# Bus_Stop_Kiosk_Rev_2.net
KiCad netlist of a schematic drawn in EAGLE
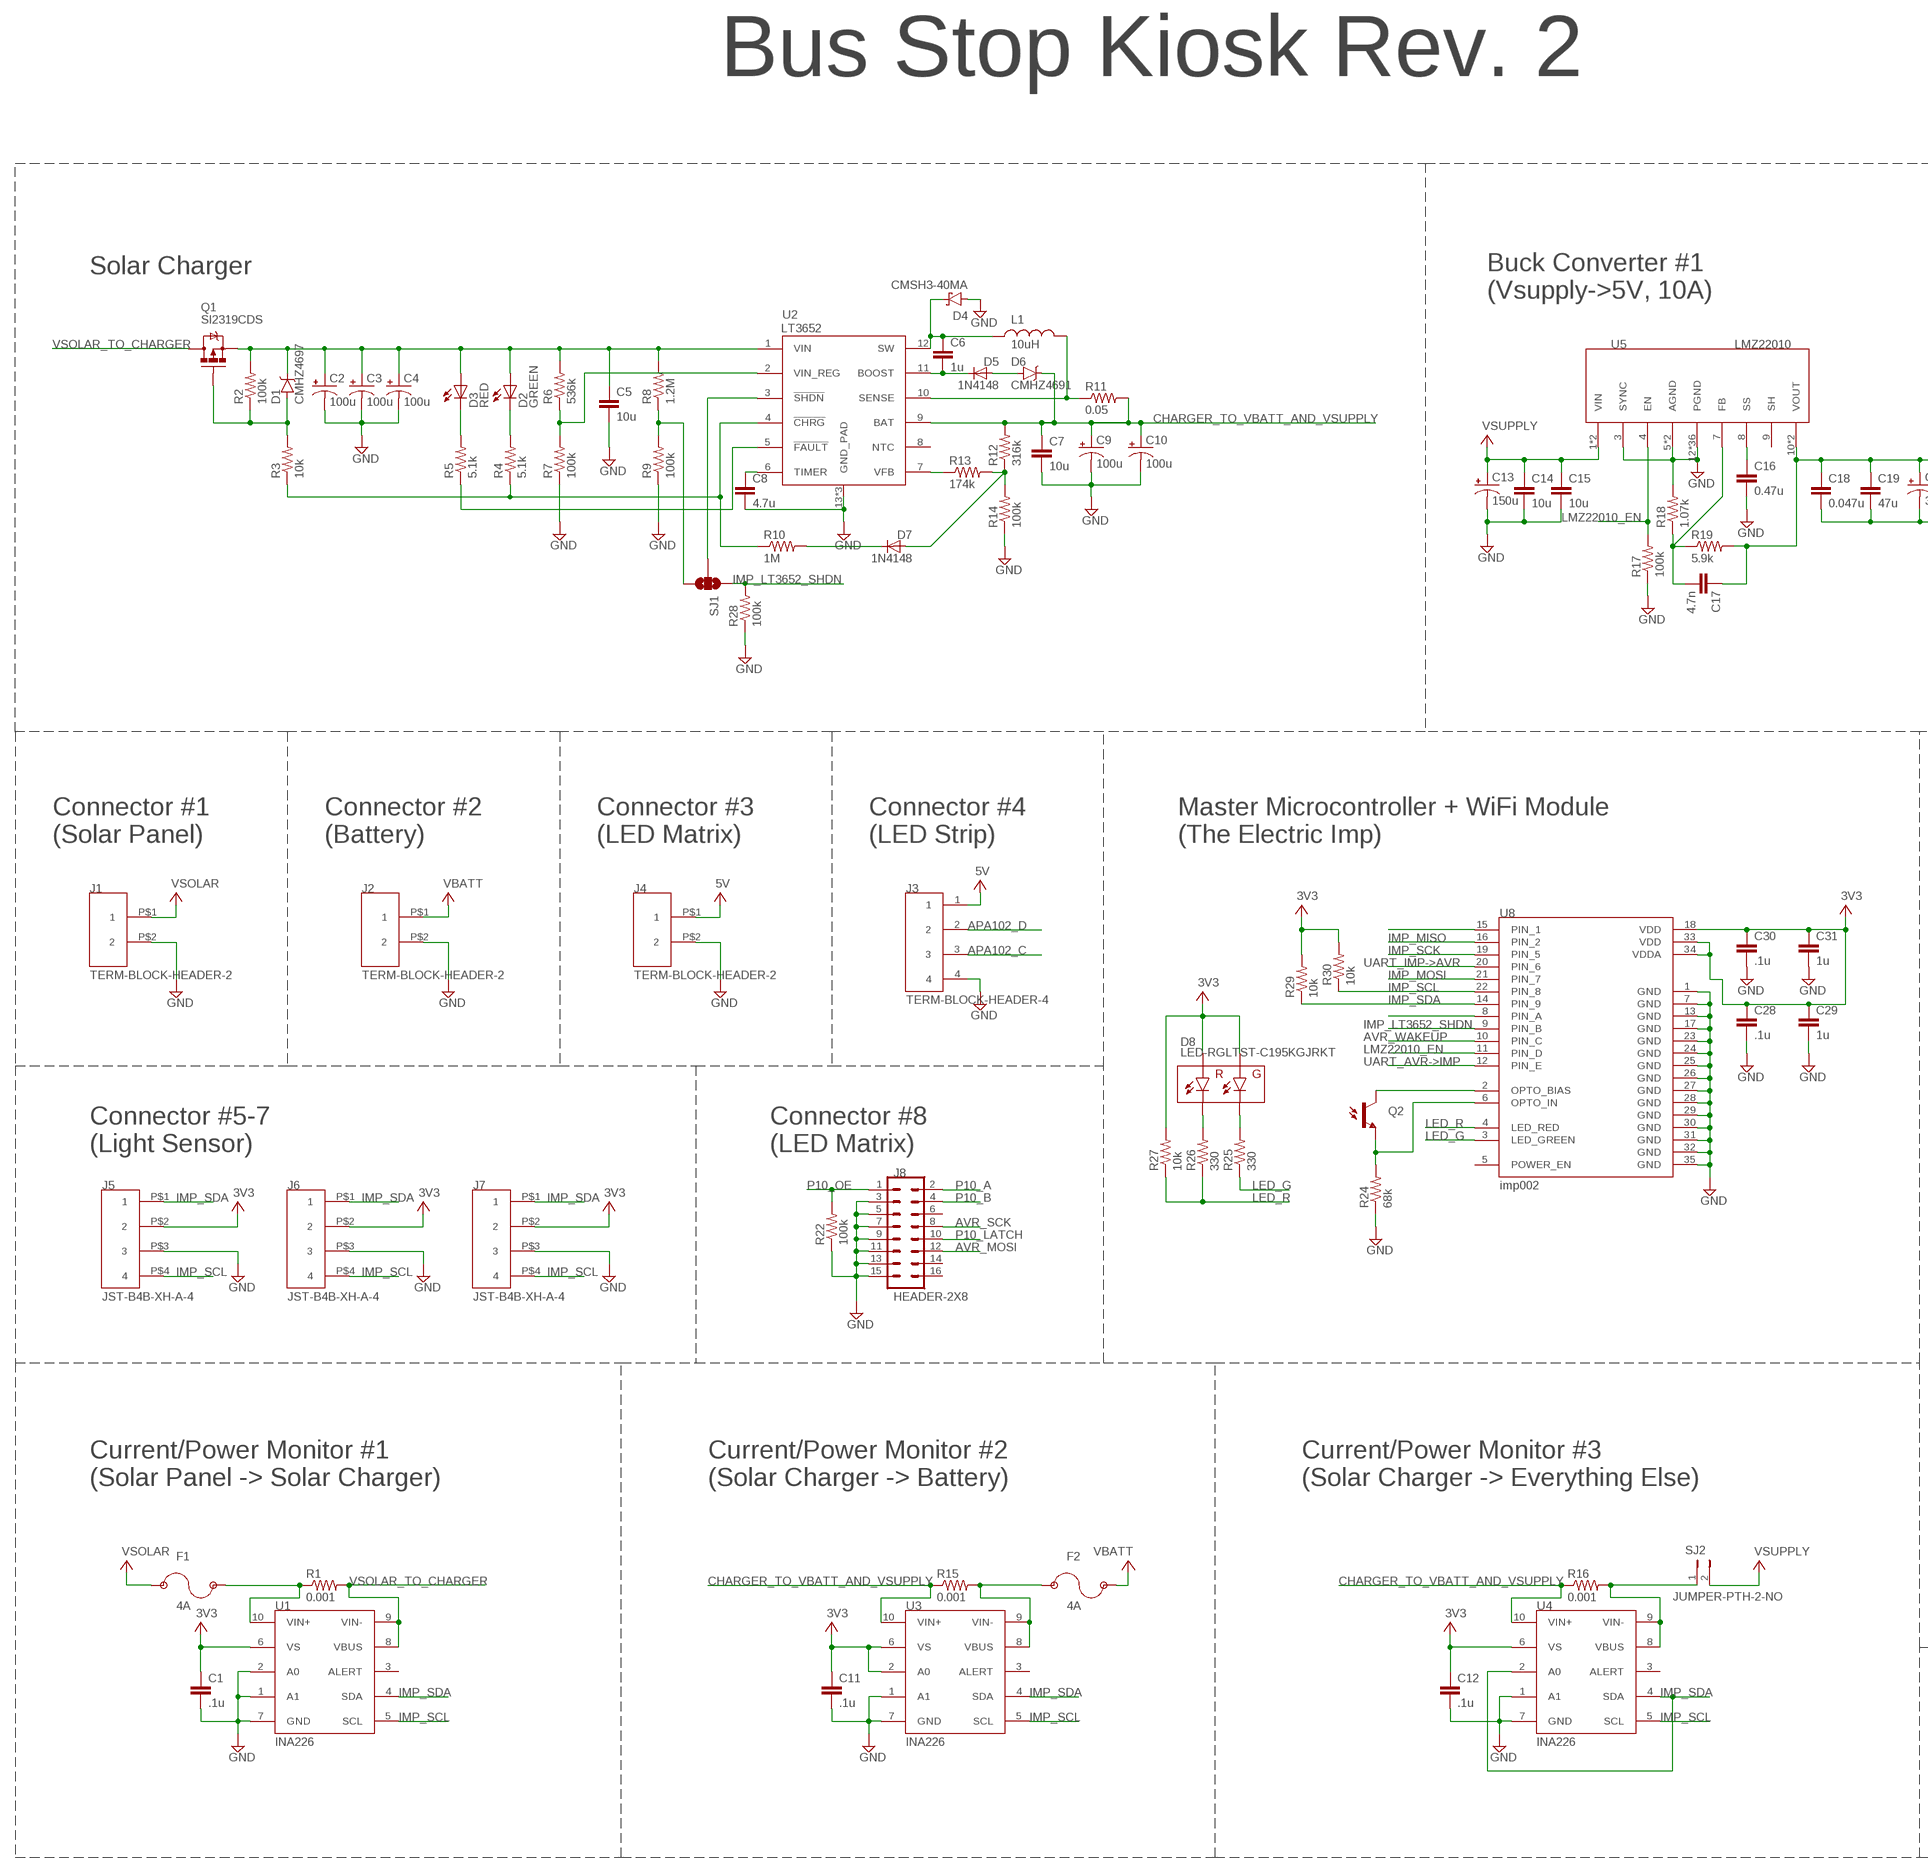
[diagram p0: schematic, sheet 1, part 1 of 2]
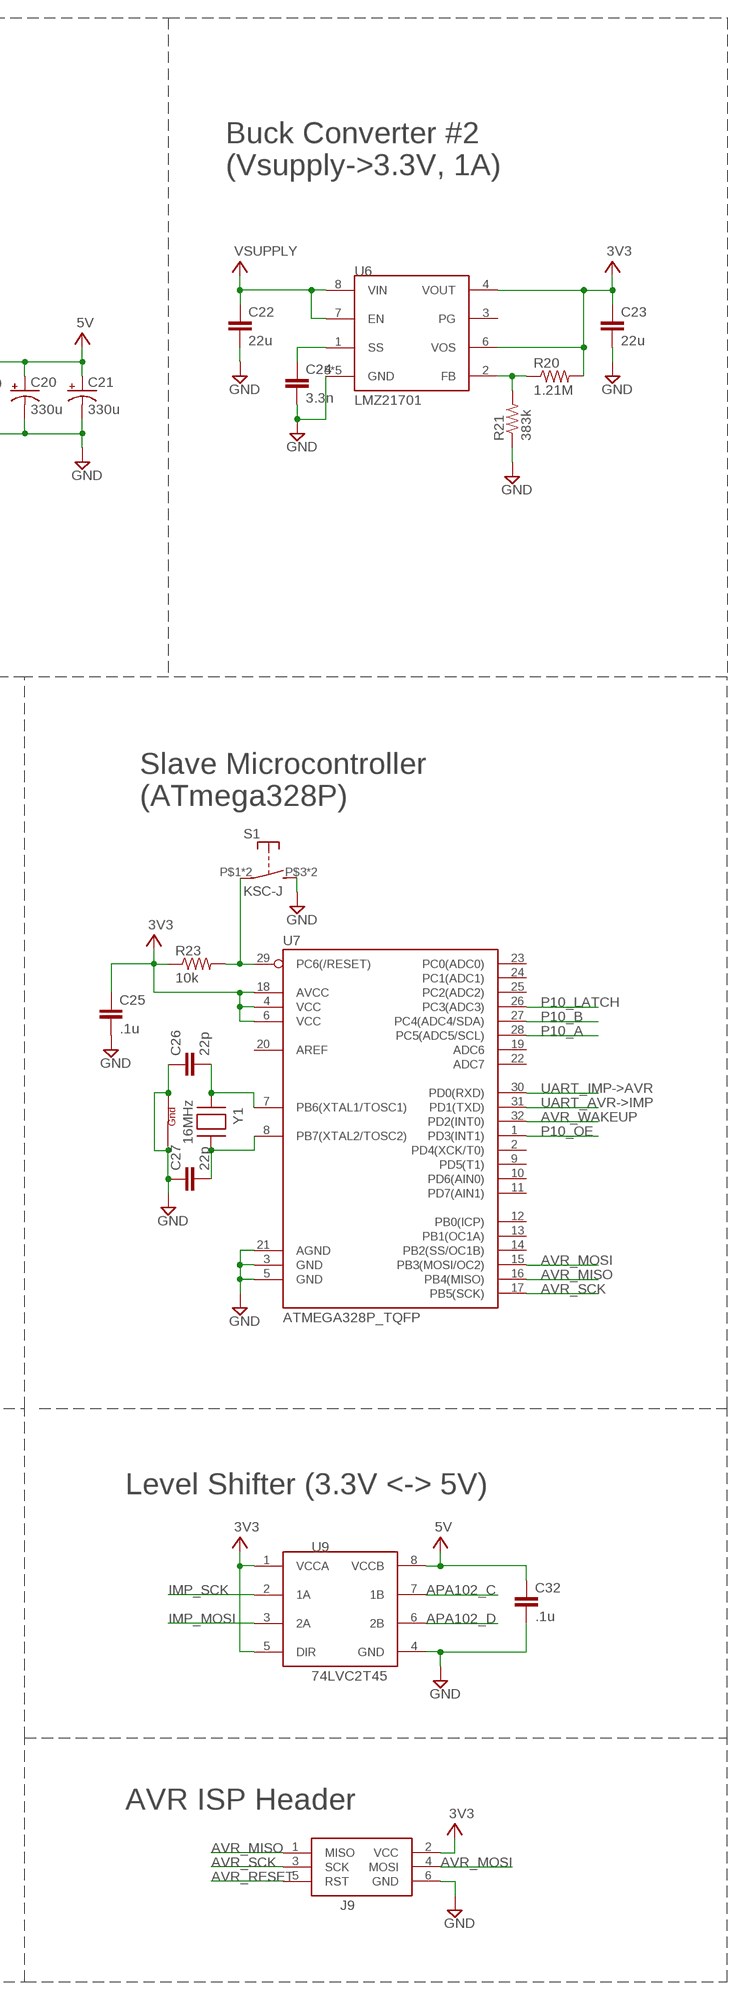
[diagram p1: schematic, sheet 1, part 2 of 2]

(export (version "E")
  (design (tool "Eeschema 10.0.6"))
  (components
    (comp (ref "C1")
      (value ".1u")
      (footprint "eagle-import:C0603K")
      (libsource (lib "eagle-import") (part "C-EUC0603K"))
    )
    (comp (ref "C2")
      (value "100u")
      (footprint "eagle-import:EIA7343")
      (libsource (lib "eagle-import") (part "CAP_POL7343"))
    )
    (comp (ref "C3")
      (value "100u")
      (footprint "eagle-import:EIA7343")
      (libsource (lib "eagle-import") (part "CAP_POL7343"))
    )
    (comp (ref "C4")
      (value "100u")
      (footprint "eagle-import:EIA7343")
      (libsource (lib "eagle-import") (part "CAP_POL7343"))
    )
    (comp (ref "C5")
      (value "10u")
      (footprint "eagle-import:C1210K")
      (libsource (lib "eagle-import") (part "C-EUC1210K"))
    )
    (comp (ref "C6")
      (value "1u")
      (footprint "eagle-import:C0805K")
      (libsource (lib "eagle-import") (part "C-EUC0805K"))
    )
    (comp (ref "C7")
      (value "10u")
      (footprint "eagle-import:C1210K")
      (libsource (lib "eagle-import") (part "C-EUC1210K"))
    )
    (comp (ref "C8")
      (value "4.7u")
      (footprint "eagle-import:C0603K")
      (libsource (lib "eagle-import") (part "C-EUC0603K"))
    )
    (comp (ref "C9")
      (value "100u")
      (footprint "eagle-import:EIA7343")
      (libsource (lib "eagle-import") (part "CAP_POL7343"))
    )
    (comp (ref "C10")
      (value "100u")
      (footprint "eagle-import:EIA7343")
      (libsource (lib "eagle-import") (part "CAP_POL7343"))
    )
    (comp (ref "C11")
      (value ".1u")
      (footprint "eagle-import:C0603K")
      (libsource (lib "eagle-import") (part "C-EUC0603K"))
    )
    (comp (ref "C12")
      (value ".1u")
      (footprint "eagle-import:C0603K")
      (libsource (lib "eagle-import") (part "C-EUC0603K"))
    )
    (comp (ref "C13")
      (value "150u")
      (footprint "eagle-import:PANASONIC_G")
      (libsource (lib "eagle-import") (part "CAP_POLG"))
    )
    (comp (ref "C14")
      (value "10u")
      (footprint "eagle-import:C1210K")
      (libsource (lib "eagle-import") (part "C-EUC1210K"))
    )
    (comp (ref "C15")
      (value "10u")
      (footprint "eagle-import:C1210K")
      (libsource (lib "eagle-import") (part "C-EUC1210K"))
    )
    (comp (ref "C16")
      (value "0.47u")
      (footprint "eagle-import:C0603K")
      (libsource (lib "eagle-import") (part "C-EUC0603K"))
    )
    (comp (ref "C17")
      (value "4.7n")
      (footprint "eagle-import:C0603K")
      (libsource (lib "eagle-import") (part "C-EUC0603K"))
    )
    (comp (ref "C18")
      (value "0.047u")
      (footprint "eagle-import:C1206K")
      (libsource (lib "eagle-import") (part "C-EUC1206K"))
    )
    (comp (ref "C19")
      (value "47u")
      (footprint "eagle-import:C1210K")
      (libsource (lib "eagle-import") (part "C-EUC1210K"))
    )
    (comp (ref "C20")
      (value "330u")
      (footprint "eagle-import:EIA7343")
      (libsource (lib "eagle-import") (part "CAP_POL7343"))
    )
    (comp (ref "C21")
      (value "330u")
      (footprint "eagle-import:EIA7343")
      (libsource (lib "eagle-import") (part "CAP_POL7343"))
    )
    (comp (ref "C22")
      (value "22u")
      (footprint "eagle-import:C1210K")
      (libsource (lib "eagle-import") (part "C-EUC1210K"))
    )
    (comp (ref "C23")
      (value "22u")
      (footprint "eagle-import:C0805K")
      (libsource (lib "eagle-import") (part "C-EUC0805K"))
    )
    (comp (ref "C24")
      (value "3.3n")
      (footprint "eagle-import:C0603K")
      (libsource (lib "eagle-import") (part "C-EUC0603K"))
    )
    (comp (ref "C25")
      (value ".1u")
      (footprint "eagle-import:C0603K")
      (libsource (lib "eagle-import") (part "C-EUC0603K"))
    )
    (comp (ref "C26")
      (value "22p")
      (footprint "eagle-import:C0603K")
      (libsource (lib "eagle-import") (part "C-EUC0603K"))
    )
    (comp (ref "C27")
      (value "22p")
      (footprint "eagle-import:C0603K")
      (libsource (lib "eagle-import") (part "C-EUC0603K"))
    )
    (comp (ref "C28")
      (value ".1u")
      (footprint "eagle-import:C0603K")
      (libsource (lib "eagle-import") (part "C-EUC0603K"))
    )
    (comp (ref "C29")
      (value "1u")
      (footprint "eagle-import:C0603K")
      (libsource (lib "eagle-import") (part "C-EUC0603K"))
    )
    (comp (ref "C30")
      (value ".1u")
      (footprint "eagle-import:C0603K")
      (libsource (lib "eagle-import") (part "C-EUC0603K"))
    )
    (comp (ref "C31")
      (value "1u")
      (footprint "eagle-import:C0603K")
      (libsource (lib "eagle-import") (part "C-EUC0603K"))
    )
    (comp (ref "C32")
      (value ".1u")
      (footprint "eagle-import:C0603K")
      (libsource (lib "eagle-import") (part "C-EUC0603K"))
    )
    (comp (ref "D1")
      (value "CMHZ4697")
      (footprint "eagle-import:SOD-123")
      (libsource (lib "eagle-import") (part "CMHZ4697"))
    )
    (comp (ref "D2")
      (value "GREEN")
      (footprint "eagle-import:CHIP-LED0603")
      (libsource (lib "eagle-import") (part "LEDCHIP-LED0603"))
    )
    (comp (ref "D3")
      (value "RED")
      (footprint "eagle-import:CHIP-LED0603")
      (libsource (lib "eagle-import") (part "LEDCHIP-LED0603"))
    )
    (comp (ref "D4")
      (value "CMSH3-40MA")
      (footprint "eagle-import:SMA-DIODE")
      (libsource (lib "eagle-import") (part "DIODE-SCHOTTKY-B340A"))
    )
    (comp (ref "D5")
      (value "1N4148")
      (footprint "eagle-import:SOD-123")
      (libsource (lib "eagle-import") (part "1N4148"))
    )
    (comp (ref "D6")
      (value "CMHZ4691")
      (footprint "eagle-import:SOD-123")
      (libsource (lib "eagle-import") (part "CMHZ4691"))
    )
    (comp (ref "D7")
      (value "1N4148")
      (footprint "eagle-import:SOD-123")
      (libsource (lib "eagle-import") (part "1N4148"))
    )
    (comp (ref "D8")
      (value "LED-RGLTST-C195KGJRKT")
      (footprint "eagle-import:LTST-C195KGJRKT")
      (libsource (lib "eagle-import") (part "LED-RGLTST-C195KGJRKT"))
    )
    (comp (ref "F1")
      (value "4A")
      (footprint "eagle-import:0603")
      (libsource (lib "eagle-import") (part "FUSE"))
    )
    (comp (ref "F2")
      (value "4A")
      (footprint "eagle-import:0603")
      (libsource (lib "eagle-import") (part "FUSE"))
    )
    (comp (ref "J1")
      (value "TERM-BLOCK-HEADER-2")
      (footprint "eagle-import:TERM-BLOCK-HDR-2")
      (libsource (lib "eagle-import") (part "TERM-BLOCK-HEADER-2"))
    )
    (comp (ref "J2")
      (value "TERM-BLOCK-HEADER-2")
      (footprint "eagle-import:TERM-BLOCK-HDR-2")
      (libsource (lib "eagle-import") (part "TERM-BLOCK-HEADER-2"))
    )
    (comp (ref "J3")
      (value "TERM-BLOCK-HEADER-4")
      (footprint "eagle-import:OSTOQ045451")
      (libsource (lib "eagle-import") (part "TERM-BLOCK-HEADER-4"))
    )
    (comp (ref "J4")
      (value "TERM-BLOCK-HEADER-2")
      (footprint "eagle-import:TERM-BLOCK-HDR-2")
      (libsource (lib "eagle-import") (part "TERM-BLOCK-HEADER-2"))
    )
    (comp (ref "J5")
      (value "JST-B4B-XH-A-4")
      (footprint "eagle-import:JST-B4B-XH-A-4")
      (libsource (lib "eagle-import") (part "JST-B4B-XH-A-4"))
    )
    (comp (ref "J6")
      (value "JST-B4B-XH-A-4")
      (footprint "eagle-import:JST-B4B-XH-A-4")
      (libsource (lib "eagle-import") (part "JST-B4B-XH-A-4"))
    )
    (comp (ref "J7")
      (value "JST-B4B-XH-A-4")
      (footprint "eagle-import:JST-B4B-XH-A-4")
      (libsource (lib "eagle-import") (part "JST-B4B-XH-A-4"))
    )
    (comp (ref "J8")
      (value "HEADER-2X8")
      (footprint "eagle-import:HEADER-2X8-SHROUDED")
      (libsource (lib "eagle-import") (part "HEADER-2X8"))
    )
    (comp (ref "J9")
      (value "AVRISP-6")
      (footprint "eagle-import:AVRISP")
      (libsource (lib "eagle-import") (part "AVRISP-6"))
    )
    (comp (ref "L1")
      (value "10uH")
      (footprint "eagle-import:INDUCTOR-6.86X6.47")
      (libsource (lib "eagle-import") (part "IHLP-2525CZ-01"))
    )
    (comp (ref "Q1")
      (value "SI2319CDS")
      (footprint "eagle-import:SOT-23-3")
      (libsource (lib "eagle-import") (part "SI2319CDS"))
    )
    (comp (ref "Q2")
      (value "PHOTOTRANSISTORPT17-21C-L41-TR8")
      (footprint "eagle-import:PT17-21C-L41-TR8")
      (libsource (lib "eagle-import") (part "PHOTOTRANSISTORPT17-21C-L41-TR8"))
    )
    (comp (ref "R1")
      (value "0.001")
      (footprint "eagle-import:R1206")
      (libsource (lib "eagle-import") (part "R-US_R1206"))
    )
    (comp (ref "R2")
      (value "100k")
      (footprint "eagle-import:R0603")
      (libsource (lib "eagle-import") (part "R-US_R0603"))
    )
    (comp (ref "R3")
      (value "10k")
      (footprint "eagle-import:R0603")
      (libsource (lib "eagle-import") (part "R-US_R0603"))
    )
    (comp (ref "R4")
      (value "5.1k")
      (footprint "eagle-import:R0402")
      (libsource (lib "eagle-import") (part "R-US_R0402"))
    )
    (comp (ref "R5")
      (value "5.1k")
      (footprint "eagle-import:R0402")
      (libsource (lib "eagle-import") (part "R-US_R0402"))
    )
    (comp (ref "R6")
      (value "536k")
      (footprint "eagle-import:R0402")
      (libsource (lib "eagle-import") (part "R-US_R0402"))
    )
    (comp (ref "R7")
      (value "100k")
      (footprint "eagle-import:R0402")
      (libsource (lib "eagle-import") (part "R-US_R0402"))
    )
    (comp (ref "R8")
      (value "1.2M")
      (footprint "eagle-import:R0402")
      (libsource (lib "eagle-import") (part "R-US_R0402"))
    )
    (comp (ref "R9")
      (value "100k")
      (footprint "eagle-import:R0402")
      (libsource (lib "eagle-import") (part "R-US_R0402"))
    )
    (comp (ref "R10")
      (value "1M")
      (footprint "eagle-import:R0402")
      (libsource (lib "eagle-import") (part "R-US_R0402"))
    )
    (comp (ref "R11")
      (value "0.05")
      (footprint "eagle-import:R1206")
      (libsource (lib "eagle-import") (part "R-US_R1206"))
    )
    (comp (ref "R12")
      (value "316k")
      (footprint "eagle-import:R0603")
      (libsource (lib "eagle-import") (part "R-US_R0603"))
    )
    (comp (ref "R13")
      (value "174k")
      (footprint "eagle-import:R0402")
      (libsource (lib "eagle-import") (part "R-US_R0402"))
    )
    (comp (ref "R14")
      (value "100k")
      (footprint "eagle-import:R0603")
      (libsource (lib "eagle-import") (part "R-US_R0603"))
    )
    (comp (ref "R15")
      (value "0.001")
      (footprint "eagle-import:R1206")
      (libsource (lib "eagle-import") (part "R-US_R1206"))
    )
    (comp (ref "R16")
      (value "0.001")
      (footprint "eagle-import:R1206")
      (libsource (lib "eagle-import") (part "R-US_R1206"))
    )
    (comp (ref "R17")
      (value "100k")
      (footprint "eagle-import:R0603")
      (libsource (lib "eagle-import") (part "R-US_R0603"))
    )
    (comp (ref "R18")
      (value "1.07k")
      (footprint "eagle-import:R0603")
      (libsource (lib "eagle-import") (part "R-US_R0603"))
    )
    (comp (ref "R19")
      (value "5.9k")
      (footprint "eagle-import:R0603")
      (libsource (lib "eagle-import") (part "R-US_R0603"))
    )
    (comp (ref "R20")
      (value "1.21M")
      (footprint "eagle-import:R0603")
      (libsource (lib "eagle-import") (part "R-US_R0603"))
    )
    (comp (ref "R21")
      (value "383k")
      (footprint "eagle-import:R0603")
      (libsource (lib "eagle-import") (part "R-US_R0603"))
    )
    (comp (ref "R22")
      (value "100k")
      (footprint "eagle-import:R0603")
      (libsource (lib "eagle-import") (part "R-US_R0603"))
    )
    (comp (ref "R23")
      (value "10k")
      (footprint "eagle-import:R0603")
      (libsource (lib "eagle-import") (part "R-US_R0603"))
    )
    (comp (ref "R24")
      (value "68k")
      (footprint "eagle-import:R0603")
      (libsource (lib "eagle-import") (part "R-US_R0603"))
    )
    (comp (ref "R25")
      (value "330")
      (footprint "eagle-import:R0603")
      (libsource (lib "eagle-import") (part "R-US_R0603"))
    )
    (comp (ref "R26")
      (value "330")
      (footprint "eagle-import:R0603")
      (libsource (lib "eagle-import") (part "R-US_R0603"))
    )
    (comp (ref "R27")
      (value "10k")
      (footprint "eagle-import:R0603")
      (libsource (lib "eagle-import") (part "R-US_R0603"))
    )
    (comp (ref "R28")
      (value "100k")
      (footprint "eagle-import:R0603")
      (libsource (lib "eagle-import") (part "R-US_R0603"))
    )
    (comp (ref "R29")
      (value "10k")
      (footprint "eagle-import:R0603")
      (libsource (lib "eagle-import") (part "R-US_R0603"))
    )
    (comp (ref "R30")
      (value "10k")
      (footprint "eagle-import:R0603")
      (libsource (lib "eagle-import") (part "R-US_R0603"))
    )
    (comp (ref "S1")
      (value "KSC-J")
      (footprint "eagle-import:C&K-KSC")
      (libsource (lib "eagle-import") (part "KSC-J"))
    )
    (comp (ref "SJ1")
      (value "JUMPER-PAD-3-NOYES_SILK")
      (footprint "eagle-import:PAD-JUMPER-3-NO_YES_SILK")
      (libsource (lib "eagle-import") (part "JUMPER-PAD-3-NOYES_SILK"))
    )
    (comp (ref "SJ2")
      (value "JUMPER-PTH-2-NO")
      (footprint "eagle-import:PTH-JUMPER-2-NO_NO_SILK")
      (libsource (lib "eagle-import") (part "JUMPER-PTH-2-NO"))
    )
    (comp (ref "U1")
      (value "INA226")
      (footprint "eagle-import:VSSOP-10")
      (libsource (lib "eagle-import") (part "INA226"))
    )
    (comp (ref "U2")
      (value "LT3652")
      (footprint "eagle-import:MSOP-12_GND")
      (libsource (lib "eagle-import") (part "LT3652"))
    )
    (comp (ref "U3")
      (value "INA226")
      (footprint "eagle-import:VSSOP-10")
      (libsource (lib "eagle-import") (part "INA226"))
    )
    (comp (ref "U4")
      (value "INA226")
      (footprint "eagle-import:VSSOP-10")
      (libsource (lib "eagle-import") (part "INA226"))
    )
    (comp (ref "U5")
      (value "LMZ22010")
      (footprint "eagle-import:TO-PMOD-11")
      (libsource (lib "eagle-import") (part "LMZ22010"))
    )
    (comp (ref "U6")
      (value "LMZ21701")
      (footprint "eagle-import:SIL0008E")
      (libsource (lib "eagle-import") (part "LMZ21701"))
    )
    (comp (ref "U7")
      (value "ATMEGA328P_TQFP")
      (footprint "eagle-import:TQFP32-08")
      (libsource (lib "eagle-import") (part "ATMEGA328P_TQFP"))
    )
    (comp (ref "U8")
      (value "imp002")
      (footprint "eagle-import:ELECTRIC_IMP_IMP002")
      (libsource (lib "eagle-import") (part "ELECTRIC_IMP_IMP002"))
    )
    (comp (ref "U9")
      (value "74LVC2T45")
      (footprint "eagle-import:VSSOP-8")
      (libsource (lib "eagle-import") (part "74LVC2T45"))
    )
    (comp (ref "Y1")
      (value "16MHz")
      (footprint "eagle-import:NX3225")
      (libsource (lib "eagle-import") (part "XTAL-4-3225"))
    )
  )
  (nets
    (net (code "1") (name "/APA102_C") (class "Default")
      (node (ref "J3") (pin "3") (pinfunction "3_3") (pintype "bidirectional"))
      (node (ref "U9") (pin "7") (pinfunction "1B_7") (pintype "bidirectional"))
    )
    (net (code "2") (name "/APA102_D") (class "Default")
      (node (ref "J3") (pin "2") (pinfunction "2_2") (pintype "bidirectional"))
      (node (ref "U9") (pin "6") (pinfunction "2B_6") (pintype "bidirectional"))
    )
    (net (code "3") (name "/AVR_MISO") (class "Default")
      (node (ref "J9") (pin "1") (pinfunction "MISO_1") (pintype "input"))
      (node (ref "U7") (pin "16") (pinfunction "PB4(MISO)_16") (pintype "bidirectional"))
    )
    (net (code "4") (name "/AVR_MOSI") (class "Default")
      (node (ref "J8") (pin "12") (pinfunction "12_12") (pintype "passive"))
      (node (ref "J9") (pin "4") (pinfunction "MOSI_4") (pintype "output"))
      (node (ref "U7") (pin "15") (pinfunction "PB3(MOSI/OC2)_15") (pintype "bidirectional"))
    )
    (net (code "5") (name "/AVR_RESET") (class "Default")
      (node (ref "J9") (pin "5") (pinfunction "RST_5") (pintype "output"))
      (node (ref "R23") (pin "2") (pinfunction "2_2") (pintype "passive"))
      (node (ref "S1") (pin "P$1") (pinfunction "P_P$1") (pintype "passive"))
      (node (ref "S1") (pin "P$2") (pinfunction "P_P$2") (pintype "passive"))
      (node (ref "U7") (pin "29") (pinfunction "PC6(/RESET)_29") (pintype "bidirectional"))
    )
    (net (code "6") (name "/AVR_SCK") (class "Default")
      (node (ref "J8") (pin "8") (pinfunction "8_8") (pintype "passive"))
      (node (ref "J9") (pin "3") (pinfunction "SCK_3") (pintype "output"))
      (node (ref "U7") (pin "17") (pinfunction "PB5(SCK)_17") (pintype "bidirectional"))
    )
    (net (code "7") (name "/AVR_WAKEUP") (class "Default")
      (node (ref "U7") (pin "32") (pinfunction "PD2(INT0)_32") (pintype "bidirectional"))
      (node (ref "U8") (pin "10") (pinfunction "PIN_C_10") (pintype "bidirectional"))
    )
    (net (code "8") (name "/CHARGER_TO_VBATT_AND_VSUPPLY") (class "Default")
      (node (ref "C10") (pin "A") (pinfunction "+_A") (pintype "passive"))
      (node (ref "C7") (pin "1") (pinfunction "1_1") (pintype "passive"))
      (node (ref "C9") (pin "A") (pinfunction "+_A") (pintype "passive"))
      (node (ref "D6") (pin "C") (pinfunction "C_C") (pintype "passive"))
      (node (ref "R11") (pin "2") (pinfunction "2_2") (pintype "passive"))
      (node (ref "R12") (pin "2") (pinfunction "2_2") (pintype "passive"))
      (node (ref "R15") (pin "1") (pinfunction "1_1") (pintype "passive"))
      (node (ref "R16") (pin "1") (pinfunction "1_1") (pintype "passive"))
      (node (ref "U2") (pin "9") (pinfunction "BAT_9") (pintype "bidirectional"))
      (node (ref "U3") (pin "10") (pinfunction "VIN+_10") (pintype "bidirectional"))
      (node (ref "U4") (pin "10") (pinfunction "VIN+_10") (pintype "bidirectional"))
    )
    (net (code "9") (name "/IMP_LT3652_SHDN") (class "Default")
      (node (ref "R28") (pin "2") (pinfunction "2_2") (pintype "passive"))
      (node (ref "SJ1") (pin "1") (pinfunction "1_1") (pintype "passive"))
      (node (ref "U8") (pin "9") (pinfunction "PIN_B_9") (pintype "bidirectional"))
    )
    (net (code "10") (name "/IMP_MISO") (class "Default")
      (node (ref "U8") (pin "16") (pinfunction "PIN_2_16") (pintype "bidirectional"))
    )
    (net (code "11") (name "/IMP_MOSI") (class "Default")
      (node (ref "U8") (pin "21") (pinfunction "PIN_7_21") (pintype "bidirectional"))
      (node (ref "U9") (pin "3") (pinfunction "2A_3") (pintype "bidirectional"))
    )
    (net (code "12") (name "/IMP_SCK") (class "Default")
      (node (ref "U8") (pin "19") (pinfunction "PIN_5_19") (pintype "bidirectional"))
      (node (ref "U9") (pin "2") (pinfunction "1A_2") (pintype "bidirectional"))
    )
    (net (code "13") (name "/IMP_SCL") (class "Default")
      (node (ref "J5") (pin "P$4") (pinfunction "4_P$4") (pintype "bidirectional"))
      (node (ref "J6") (pin "P$4") (pinfunction "4_P$4") (pintype "bidirectional"))
      (node (ref "J7") (pin "P$4") (pinfunction "4_P$4") (pintype "bidirectional"))
      (node (ref "R30") (pin "1") (pinfunction "1_1") (pintype "passive"))
      (node (ref "U1") (pin "5") (pinfunction "SCL_5") (pintype "bidirectional"))
      (node (ref "U3") (pin "5") (pinfunction "SCL_5") (pintype "bidirectional"))
      (node (ref "U4") (pin "5") (pinfunction "SCL_5") (pintype "bidirectional"))
      (node (ref "U8") (pin "22") (pinfunction "PIN_8_22") (pintype "bidirectional"))
    )
    (net (code "14") (name "/IMP_SDA") (class "Default")
      (node (ref "J5") (pin "P$1") (pinfunction "1_P$1") (pintype "bidirectional"))
      (node (ref "J6") (pin "P$1") (pinfunction "1_P$1") (pintype "bidirectional"))
      (node (ref "J7") (pin "P$1") (pinfunction "1_P$1") (pintype "bidirectional"))
      (node (ref "R29") (pin "1") (pinfunction "1_1") (pintype "passive"))
      (node (ref "U1") (pin "4") (pinfunction "SDA_4") (pintype "bidirectional"))
      (node (ref "U3") (pin "4") (pinfunction "SDA_4") (pintype "bidirectional"))
      (node (ref "U4") (pin "2") (pinfunction "A0_2") (pintype "bidirectional"))
      (node (ref "U4") (pin "4") (pinfunction "SDA_4") (pintype "bidirectional"))
      (node (ref "U8") (pin "14") (pinfunction "PIN_9_14") (pintype "bidirectional"))
    )
    (net (code "15") (name "/LED_G") (class "Default")
      (node (ref "R25") (pin "1") (pinfunction "1_1") (pintype "passive"))
      (node (ref "U8") (pin "3") (pinfunction "LED_GREEN_3") (pintype "bidirectional"))
    )
    (net (code "16") (name "/LED_R") (class "Default")
      (node (ref "R26") (pin "1") (pinfunction "1_1") (pintype "passive"))
      (node (ref "R27") (pin "1") (pinfunction "1_1") (pintype "passive"))
      (node (ref "U8") (pin "4") (pinfunction "LED_RED_4") (pintype "bidirectional"))
    )
    (net (code "17") (name "/LMZ22010_EN") (class "Default")
      (node (ref "R17") (pin "2") (pinfunction "2_2") (pintype "passive"))
      (node (ref "U5") (pin "4") (pinfunction "EN_4") (pintype "bidirectional"))
      (node (ref "U8") (pin "11") (pinfunction "PIN_D_11") (pintype "bidirectional"))
    )
    (net (code "18") (name "/P10_A") (class "Default")
      (node (ref "J8") (pin "2") (pinfunction "2_2") (pintype "passive"))
      (node (ref "U7") (pin "28") (pinfunction "PC5(ADC5/SCL)_28") (pintype "bidirectional"))
    )
    (net (code "19") (name "/P10_B") (class "Default")
      (node (ref "J8") (pin "4") (pinfunction "4_4") (pintype "passive"))
      (node (ref "U7") (pin "27") (pinfunction "PC4(ADC4/SDA)_27") (pintype "bidirectional"))
    )
    (net (code "20") (name "/P10_LATCH") (class "Default")
      (node (ref "J8") (pin "10") (pinfunction "10_10") (pintype "passive"))
      (node (ref "U7") (pin "26") (pinfunction "PC3(ADC3)_26") (pintype "bidirectional"))
    )
    (net (code "21") (name "/P10_OE") (class "Default")
      (node (ref "J8") (pin "1") (pinfunction "1_1") (pintype "passive"))
      (node (ref "R22") (pin "2") (pinfunction "2_2") (pintype "passive"))
      (node (ref "U7") (pin "1") (pinfunction "PD3(INT1)_1") (pintype "bidirectional"))
    )
    (net (code "22") (name "/UART_AVR->IMP") (class "Default")
      (node (ref "U7") (pin "31") (pinfunction "PD1(TXD)_31") (pintype "bidirectional"))
      (node (ref "U8") (pin "12") (pinfunction "PIN_E_12") (pintype "bidirectional"))
    )
    (net (code "23") (name "/UART_IMP->AVR") (class "Default")
      (node (ref "U7") (pin "30") (pinfunction "PD0(RXD)_30") (pintype "bidirectional"))
      (node (ref "U8") (pin "20") (pinfunction "PIN_6_20") (pintype "bidirectional"))
    )
    (net (code "24") (name "/VSOLAR_TO_CHARGER") (class "Default")
      (node (ref "Q1") (pin "3") (pinfunction "D_3") (pintype "passive"))
      (node (ref "R1") (pin "2") (pinfunction "2_2") (pintype "passive"))
      (node (ref "U1") (pin "8") (pinfunction "VBUS_8") (pintype "power_in"))
      (node (ref "U1") (pin "9") (pinfunction "VIN-_9") (pintype "bidirectional"))
    )
    (net (code "25") (name "3V3") (class "Default")
      (node (ref "C1") (pin "1") (pinfunction "1_1") (pintype "passive"))
      (node (ref "C11") (pin "1") (pinfunction "1_1") (pintype "passive"))
      (node (ref "C12") (pin "1") (pinfunction "1_1") (pintype "passive"))
      (node (ref "C23") (pin "1") (pinfunction "1_1") (pintype "passive"))
      (node (ref "C25") (pin "1") (pinfunction "1_1") (pintype "passive"))
      (node (ref "C28") (pin "1") (pinfunction "1_1") (pintype "passive"))
      (node (ref "C29") (pin "1") (pinfunction "1_1") (pintype "passive"))
      (node (ref "C30") (pin "1") (pinfunction "1_1") (pintype "passive"))
      (node (ref "C31") (pin "1") (pinfunction "1_1") (pintype "passive"))
      (node (ref "D8") (pin "P$1") (pinfunction "GA_P$1") (pintype "passive"))
      (node (ref "D8") (pin "P$2") (pinfunction "RA_P$2") (pintype "passive"))
      (node (ref "J5") (pin "P$2") (pinfunction "2_P$2") (pintype "bidirectional"))
      (node (ref "J6") (pin "P$2") (pinfunction "2_P$2") (pintype "bidirectional"))
      (node (ref "J7") (pin "P$2") (pinfunction "2_P$2") (pintype "bidirectional"))
      (node (ref "J9") (pin "2") (pinfunction "VCC_2") (pintype "power_in"))
      (node (ref "R20") (pin "2") (pinfunction "2_2") (pintype "passive"))
      (node (ref "R23") (pin "1") (pinfunction "1_1") (pintype "passive"))
      (node (ref "R27") (pin "2") (pinfunction "2_2") (pintype "passive"))
      (node (ref "R29") (pin "2") (pinfunction "2_2") (pintype "passive"))
      (node (ref "R30") (pin "2") (pinfunction "2_2") (pintype "passive"))
      (node (ref "U1") (pin "6") (pinfunction "VS_6") (pintype "power_in"))
      (node (ref "U3") (pin "2") (pinfunction "A0_2") (pintype "bidirectional"))
      (node (ref "U3") (pin "6") (pinfunction "VS_6") (pintype "power_in"))
      (node (ref "U4") (pin "6") (pinfunction "VS_6") (pintype "power_in"))
      (node (ref "U6") (pin "4") (pinfunction "VOUT_4") (pintype "bidirectional"))
      (node (ref "U6") (pin "6") (pinfunction "VOS_6") (pintype "bidirectional"))
      (node (ref "U7") (pin "18") (pinfunction "AVCC_18") (pintype "bidirectional"))
      (node (ref "U7") (pin "4") (pinfunction "VCC_4") (pintype "bidirectional"))
      (node (ref "U7") (pin "6") (pinfunction "VCC_6") (pintype "bidirectional"))
      (node (ref "U8") (pin "18") (pinfunction "VDD_18") (pintype "bidirectional"))
      (node (ref "U8") (pin "33") (pinfunction "VDD_33") (pintype "bidirectional"))
      (node (ref "U8") (pin "34") (pinfunction "VDDA_34") (pintype "bidirectional"))
      (node (ref "U9") (pin "1") (pinfunction "VCCA_1") (pintype "bidirectional"))
      (node (ref "U9") (pin "5") (pinfunction "DIR_5") (pintype "bidirectional"))
    )
    (net (code "26") (name "5V") (class "Default")
      (node (ref "C17") (pin "1") (pinfunction "1_1") (pintype "passive"))
      (node (ref "C18") (pin "1") (pinfunction "1_1") (pintype "passive"))
      (node (ref "C19") (pin "1") (pinfunction "1_1") (pintype "passive"))
      (node (ref "C20") (pin "A") (pinfunction "+_A") (pintype "passive"))
      (node (ref "C21") (pin "A") (pinfunction "+_A") (pintype "passive"))
      (node (ref "C32") (pin "1") (pinfunction "1_1") (pintype "passive"))
      (node (ref "J3") (pin "1") (pinfunction "1_1") (pintype "bidirectional"))
      (node (ref "J4") (pin "P$1") (pinfunction "1_P$1") (pintype "bidirectional"))
      (node (ref "R19") (pin "2") (pinfunction "2_2") (pintype "passive"))
      (node (ref "U5") (pin "10") (pinfunction "VOUT_10") (pintype "bidirectional"))
      (node (ref "U5") (pin "11") (pinfunction "VOUT_11") (pintype "bidirectional"))
      (node (ref "U9") (pin "8") (pinfunction "VCCB_8") (pintype "bidirectional"))
    )
    (net (code "27") (name "GND") (class "Default")
      (node (ref "C1") (pin "2") (pinfunction "2_2") (pintype "passive"))
      (node (ref "C10") (pin "C") (pinfunction "-_C") (pintype "passive"))
      (node (ref "C11") (pin "2") (pinfunction "2_2") (pintype "passive"))
      (node (ref "C12") (pin "2") (pinfunction "2_2") (pintype "passive"))
      (node (ref "C13") (pin "-") (pinfunction "-_-") (pintype "passive"))
      (node (ref "C14") (pin "2") (pinfunction "2_2") (pintype "passive"))
      (node (ref "C15") (pin "2") (pinfunction "2_2") (pintype "passive"))
      (node (ref "C16") (pin "2") (pinfunction "2_2") (pintype "passive"))
      (node (ref "C18") (pin "2") (pinfunction "2_2") (pintype "passive"))
      (node (ref "C19") (pin "2") (pinfunction "2_2") (pintype "passive"))
      (node (ref "C2") (pin "C") (pinfunction "-_C") (pintype "passive"))
      (node (ref "C20") (pin "C") (pinfunction "-_C") (pintype "passive"))
      (node (ref "C21") (pin "C") (pinfunction "-_C") (pintype "passive"))
      (node (ref "C22") (pin "2") (pinfunction "2_2") (pintype "passive"))
      (node (ref "C23") (pin "2") (pinfunction "2_2") (pintype "passive"))
      (node (ref "C24") (pin "2") (pinfunction "2_2") (pintype "passive"))
      (node (ref "C25") (pin "2") (pinfunction "2_2") (pintype "passive"))
      (node (ref "C26") (pin "1") (pinfunction "1_1") (pintype "passive"))
      (node (ref "C27") (pin "1") (pinfunction "1_1") (pintype "passive"))
      (node (ref "C28") (pin "2") (pinfunction "2_2") (pintype "passive"))
      (node (ref "C29") (pin "2") (pinfunction "2_2") (pintype "passive"))
      (node (ref "C3") (pin "C") (pinfunction "-_C") (pintype "passive"))
      (node (ref "C30") (pin "2") (pinfunction "2_2") (pintype "passive"))
      (node (ref "C31") (pin "2") (pinfunction "2_2") (pintype "passive"))
      (node (ref "C32") (pin "2") (pinfunction "2_2") (pintype "passive"))
      (node (ref "C4") (pin "C") (pinfunction "-_C") (pintype "passive"))
      (node (ref "C5") (pin "2") (pinfunction "2_2") (pintype "passive"))
      (node (ref "C7") (pin "2") (pinfunction "2_2") (pintype "passive"))
      (node (ref "C8") (pin "2") (pinfunction "2_2") (pintype "passive"))
      (node (ref "C9") (pin "C") (pinfunction "-_C") (pintype "passive"))
      (node (ref "D4") (pin "A") (pinfunction "A_A") (pintype "passive"))
      (node (ref "J1") (pin "P$2") (pinfunction "2_P$2") (pintype "bidirectional"))
      (node (ref "J2") (pin "P$2") (pinfunction "2_P$2") (pintype "bidirectional"))
      (node (ref "J3") (pin "4") (pinfunction "4_4") (pintype "bidirectional"))
      (node (ref "J4") (pin "P$2") (pinfunction "2_P$2") (pintype "bidirectional"))
      (node (ref "J5") (pin "P$3") (pinfunction "3_P$3") (pintype "bidirectional"))
      (node (ref "J6") (pin "P$3") (pinfunction "3_P$3") (pintype "bidirectional"))
      (node (ref "J7") (pin "P$3") (pinfunction "3_P$3") (pintype "bidirectional"))
      (node (ref "J8") (pin "11") (pinfunction "11_11") (pintype "passive"))
      (node (ref "J8") (pin "13") (pinfunction "13_13") (pintype "passive"))
      (node (ref "J8") (pin "15") (pinfunction "15_15") (pintype "passive"))
      (node (ref "J8") (pin "3") (pinfunction "3_3") (pintype "passive"))
      (node (ref "J8") (pin "5") (pinfunction "5_5") (pintype "passive"))
      (node (ref "J8") (pin "7") (pinfunction "7_7") (pintype "passive"))
      (node (ref "J8") (pin "9") (pinfunction "9_9") (pintype "passive"))
      (node (ref "J9") (pin "6") (pinfunction "GND_6") (pintype "power_in"))
      (node (ref "R14") (pin "1") (pinfunction "1_1") (pintype "passive"))
      (node (ref "R17") (pin "1") (pinfunction "1_1") (pintype "passive"))
      (node (ref "R18") (pin "2") (pinfunction "2_2") (pintype "passive"))
      (node (ref "R21") (pin "1") (pinfunction "1_1") (pintype "passive"))
      (node (ref "R22") (pin "1") (pinfunction "1_1") (pintype "passive"))
      (node (ref "R24") (pin "1") (pinfunction "1_1") (pintype "passive"))
      (node (ref "R28") (pin "1") (pinfunction "1_1") (pintype "passive"))
      (node (ref "R7") (pin "1") (pinfunction "1_1") (pintype "passive"))
      (node (ref "R9") (pin "1") (pinfunction "1_1") (pintype "passive"))
      (node (ref "S1") (pin "P$3") (pinfunction "S_P$3") (pintype "passive"))
      (node (ref "S1") (pin "P$4") (pinfunction "S_P$4") (pintype "passive"))
      (node (ref "U1") (pin "1") (pinfunction "A1_1") (pintype "bidirectional"))
      (node (ref "U1") (pin "2") (pinfunction "A0_2") (pintype "bidirectional"))
      (node (ref "U1") (pin "7") (pinfunction "GND_7") (pintype "power_in"))
      (node (ref "U2") (pin "13") (pinfunction "GND_PAD_13") (pintype "bidirectional"))
      (node (ref "U2") (pin "P$1") (pinfunction "GND_PAD_P$1") (pintype "bidirectional"))
      (node (ref "U2") (pin "P$2") (pinfunction "GND_PAD_P$2") (pintype "bidirectional"))
      (node (ref "U3") (pin "1") (pinfunction "A1_1") (pintype "bidirectional"))
      (node (ref "U3") (pin "7") (pinfunction "GND_7") (pintype "power_in"))
      (node (ref "U4") (pin "1") (pinfunction "A1_1") (pintype "bidirectional"))
      (node (ref "U4") (pin "7") (pinfunction "GND_7") (pintype "power_in"))
      (node (ref "U5") (pin "12") (pinfunction "PGND_12") (pintype "bidirectional"))
      (node (ref "U5") (pin "3") (pinfunction "SYNC_3") (pintype "bidirectional"))
      (node (ref "U5") (pin "5") (pinfunction "AGND_5") (pintype "bidirectional"))
      (node (ref "U5") (pin "6") (pinfunction "AGND_6") (pintype "bidirectional"))
      (node (ref "U5") (pin "P$1") (pinfunction "PGND_P$1") (pintype "bidirectional"))
      (node (ref "U5") (pin "P$10") (pinfunction "PGND_P$10") (pintype "bidirectional"))
      (node (ref "U5") (pin "P$11") (pinfunction "PGND_P$11") (pintype "bidirectional"))
      (node (ref "U5") (pin "P$12") (pinfunction "PGND_P$12") (pintype "bidirectional"))
      (node (ref "U5") (pin "P$13") (pinfunction "PGND_P$13") (pintype "bidirectional"))
      (node (ref "U5") (pin "P$14") (pinfunction "PGND_P$14") (pintype "bidirectional"))
      (node (ref "U5") (pin "P$15") (pinfunction "PGND_P$15") (pintype "bidirectional"))
      (node (ref "U5") (pin "P$16") (pinfunction "PGND_P$16") (pintype "bidirectional"))
      (node (ref "U5") (pin "P$17") (pinfunction "PGND_P$17") (pintype "bidirectional"))
      (node (ref "U5") (pin "P$18") (pinfunction "PGND_P$18") (pintype "bidirectional"))
      (node (ref "U5") (pin "P$19") (pinfunction "PGND_P$19") (pintype "bidirectional"))
      (node (ref "U5") (pin "P$2") (pinfunction "PGND_P$2") (pintype "bidirectional"))
      (node (ref "U5") (pin "P$20") (pinfunction "PGND_P$20") (pintype "bidirectional"))
      (node (ref "U5") (pin "P$21") (pinfunction "PGND_P$21") (pintype "bidirectional"))
      (node (ref "U5") (pin "P$22") (pinfunction "PGND_P$22") (pintype "bidirectional"))
      (node (ref "U5") (pin "P$23") (pinfunction "PGND_P$23") (pintype "bidirectional"))
      (node (ref "U5") (pin "P$24") (pinfunction "PGND_P$24") (pintype "bidirectional"))
      (node (ref "U5") (pin "P$25") (pinfunction "PGND_P$25") (pintype "bidirectional"))
      (node (ref "U5") (pin "P$26") (pinfunction "PGND_P$26") (pintype "bidirectional"))
      (node (ref "U5") (pin "P$27") (pinfunction "PGND_P$27") (pintype "bidirectional"))
      (node (ref "U5") (pin "P$28") (pinfunction "PGND_P$28") (pintype "bidirectional"))
      (node (ref "U5") (pin "P$29") (pinfunction "PGND_P$29") (pintype "bidirectional"))
      (node (ref "U5") (pin "P$3") (pinfunction "PGND_P$3") (pintype "bidirectional"))
      (node (ref "U5") (pin "P$30") (pinfunction "PGND_P$30") (pintype "bidirectional"))
      (node (ref "U5") (pin "P$31") (pinfunction "PGND_P$31") (pintype "bidirectional"))
      (node (ref "U5") (pin "P$32") (pinfunction "PGND_P$32") (pintype "bidirectional"))
      (node (ref "U5") (pin "P$33") (pinfunction "PGND_P$33") (pintype "bidirectional"))
      (node (ref "U5") (pin "P$34") (pinfunction "PGND_P$34") (pintype "bidirectional"))
      (node (ref "U5") (pin "P$35") (pinfunction "PGND_P$35") (pintype "bidirectional"))
      (node (ref "U5") (pin "P$4") (pinfunction "PGND_P$4") (pintype "bidirectional"))
      (node (ref "U5") (pin "P$5") (pinfunction "PGND_P$5") (pintype "bidirectional"))
      (node (ref "U5") (pin "P$6") (pinfunction "PGND_P$6") (pintype "bidirectional"))
      (node (ref "U5") (pin "P$7") (pinfunction "PGND_P$7") (pintype "bidirectional"))
      (node (ref "U5") (pin "P$8") (pinfunction "PGND_P$8") (pintype "bidirectional"))
      (node (ref "U5") (pin "P$9") (pinfunction "PGND_P$9") (pintype "bidirectional"))
      (node (ref "U6") (pin "10") (pinfunction "GND_10") (pintype "bidirectional"))
      (node (ref "U6") (pin "11") (pinfunction "GND_11") (pintype "bidirectional"))
      (node (ref "U6") (pin "12") (pinfunction "GND_12") (pintype "bidirectional"))
      (node (ref "U6") (pin "5") (pinfunction "GND_5") (pintype "bidirectional"))
      (node (ref "U6") (pin "9") (pinfunction "GND_9") (pintype "bidirectional"))
      (node (ref "U7") (pin "21") (pinfunction "AGND_21") (pintype "bidirectional"))
      (node (ref "U7") (pin "3") (pinfunction "GND_3") (pintype "bidirectional"))
      (node (ref "U7") (pin "5") (pinfunction "GND_5") (pintype "bidirectional"))
      (node (ref "U8") (pin "1") (pinfunction "GND_1") (pintype "bidirectional"))
      (node (ref "U8") (pin "13") (pinfunction "GND_13") (pintype "bidirectional"))
      (node (ref "U8") (pin "17") (pinfunction "GND_17") (pintype "bidirectional"))
      (node (ref "U8") (pin "23") (pinfunction "GND_23") (pintype "bidirectional"))
      (node (ref "U8") (pin "24") (pinfunction "GND_24") (pintype "bidirectional"))
      (node (ref "U8") (pin "25") (pinfunction "GND_25") (pintype "bidirectional"))
      (node (ref "U8") (pin "26") (pinfunction "GND_26") (pintype "bidirectional"))
      (node (ref "U8") (pin "27") (pinfunction "GND_27") (pintype "bidirectional"))
      (node (ref "U8") (pin "28") (pinfunction "GND_28") (pintype "bidirectional"))
      (node (ref "U8") (pin "29") (pinfunction "GND_29") (pintype "bidirectional"))
      (node (ref "U8") (pin "30") (pinfunction "GND_30") (pintype "bidirectional"))
      (node (ref "U8") (pin "31") (pinfunction "GND_31") (pintype "bidirectional"))
      (node (ref "U8") (pin "32") (pinfunction "GND_32") (pintype "bidirectional"))
      (node (ref "U8") (pin "35") (pinfunction "GND_35") (pintype "bidirectional"))
      (node (ref "U8") (pin "7") (pinfunction "GND_7") (pintype "bidirectional"))
      (node (ref "U9") (pin "4") (pinfunction "GND_4") (pintype "bidirectional"))
      (node (ref "Y1") (pin "2") (pinfunction "G2_2") (pintype "power_in"))
      (node (ref "Y1") (pin "4") (pinfunction "G1_4") (pintype "power_in"))
    )
    (net (code "28") (name "Net-(C2-+)") (class "Default")
      (node (ref "C2") (pin "A") (pinfunction "+_A") (pintype "passive"))
      (node (ref "C3") (pin "A") (pinfunction "+_A") (pintype "passive"))
      (node (ref "C4") (pin "A") (pinfunction "+_A") (pintype "passive"))
      (node (ref "C5") (pin "1") (pinfunction "1_1") (pintype "passive"))
      (node (ref "D1") (pin "C") (pinfunction "C_C") (pintype "passive"))
      (node (ref "D2") (pin "A") (pinfunction "A_A") (pintype "passive"))
      (node (ref "D3") (pin "A") (pinfunction "A_A") (pintype "passive"))
      (node (ref "Q1") (pin "2") (pinfunction "S_2") (pintype "passive"))
      (node (ref "R2") (pin "2") (pinfunction "2_2") (pintype "passive"))
      (node (ref "R6") (pin "2") (pinfunction "2_2") (pintype "passive"))
      (node (ref "R8") (pin "2") (pinfunction "2_2") (pintype "passive"))
      (node (ref "U2") (pin "1") (pinfunction "VIN_1") (pintype "bidirectional"))
    )
    (net (code "29") (name "Net-(D2-PadC)") (class "Default")
      (node (ref "D2") (pin "C") (pinfunction "C_C") (pintype "passive"))
      (node (ref "R4") (pin "2") (pinfunction "2_2") (pintype "passive"))
    )
    (net (code "30") (name "Net-(D3-PadC)") (class "Default")
      (node (ref "D3") (pin "C") (pinfunction "C_C") (pintype "passive"))
      (node (ref "R5") (pin "2") (pinfunction "2_2") (pintype "passive"))
    )
    (net (code "31") (name "Net-(D5-PadA)") (class "Default")
      (node (ref "D5") (pin "A") (pinfunction "A_A") (pintype "passive"))
      (node (ref "D6") (pin "A") (pinfunction "A_A") (pintype "passive"))
    )
    (net (code "32") (name "Net-(D7-PadA)") (class "Default")
      (node (ref "D7") (pin "A") (pinfunction "A_A") (pintype "passive"))
      (node (ref "R12") (pin "1") (pinfunction "1_1") (pintype "passive"))
      (node (ref "R13") (pin "2") (pinfunction "2_2") (pintype "passive"))
      (node (ref "R14") (pin "2") (pinfunction "2_2") (pintype "passive"))
    )
    (net (code "33") (name "Net-(D7-PadC)") (class "Default")
      (node (ref "D7") (pin "C") (pinfunction "C_C") (pintype "passive"))
      (node (ref "R10") (pin "2") (pinfunction "2_2") (pintype "passive"))
    )
    (net (code "34") (name "Net-(D8-GC)") (class "Default")
      (node (ref "D8") (pin "P$3") (pinfunction "GC_P$3") (pintype "passive"))
      (node (ref "R25") (pin "2") (pinfunction "2_2") (pintype "passive"))
    )
    (net (code "35") (name "Net-(D8-RC)") (class "Default")
      (node (ref "D8") (pin "P$4") (pinfunction "RC_P$4") (pintype "passive"))
      (node (ref "R26") (pin "2") (pinfunction "2_2") (pintype "passive"))
    )
    (net (code "36") (name "Net-(F1-P$2)") (class "Default")
      (node (ref "F1") (pin "2") (pinfunction "P$2_2") (pintype "bidirectional"))
      (node (ref "R1") (pin "1") (pinfunction "1_1") (pintype "passive"))
      (node (ref "U1") (pin "10") (pinfunction "VIN+_10") (pintype "bidirectional"))
    )
    (net (code "37") (name "Net-(F2-P$1)") (class "Default")
      (node (ref "F2") (pin "1") (pinfunction "P$1_1") (pintype "bidirectional"))
      (node (ref "R15") (pin "2") (pinfunction "2_2") (pintype "passive"))
      (node (ref "U3") (pin "8") (pinfunction "VBUS_8") (pintype "power_in"))
      (node (ref "U3") (pin "9") (pinfunction "VIN-_9") (pintype "bidirectional"))
    )
    (net (code "38") (name "Net-(L1-1)") (class "Default")
      (node (ref "C6") (pin "1") (pinfunction "1_1") (pintype "passive"))
      (node (ref "D4") (pin "C") (pinfunction "C_C") (pintype "passive"))
      (node (ref "L1") (pin "P$1") (pinfunction "1_P$1") (pintype "passive"))
      (node (ref "U2") (pin "12") (pinfunction "SW_12") (pintype "bidirectional"))
    )
    (net (code "39") (name "Net-(L1-2)") (class "Default")
      (node (ref "L1") (pin "P$2") (pinfunction "2_P$2") (pintype "passive"))
      (node (ref "R11") (pin "1") (pinfunction "1_1") (pintype "passive"))
      (node (ref "U2") (pin "10") (pinfunction "SENSE_10") (pintype "bidirectional"))
    )
    (net (code "40") (name "Net-(Q1-G)") (class "Default")
      (node (ref "D1") (pin "A") (pinfunction "A_A") (pintype "passive"))
      (node (ref "Q1") (pin "1") (pinfunction "G_1") (pintype "passive"))
      (node (ref "R2") (pin "1") (pinfunction "1_1") (pintype "passive"))
      (node (ref "R3") (pin "2") (pinfunction "2_2") (pintype "passive"))
    )
    (net (code "41") (name "Net-(R8-Pad1)") (class "Default")
      (node (ref "R8") (pin "1") (pinfunction "1_1") (pintype "passive"))
      (node (ref "R9") (pin "2") (pinfunction "2_2") (pintype "passive"))
      (node (ref "SJ1") (pin "3") (pinfunction "3_3") (pintype "passive"))
    )
    (net (code "42") (name "Net-(U2-BOOST)") (class "Default")
      (node (ref "C6") (pin "2") (pinfunction "2_2") (pintype "passive"))
      (node (ref "D5") (pin "C") (pinfunction "C_C") (pintype "passive"))
      (node (ref "U2") (pin "11") (pinfunction "BOOST_11") (pintype "bidirectional"))
    )
    (net (code "43") (name "Net-(U2-TIMER)") (class "Default")
      (node (ref "C8") (pin "1") (pinfunction "1_1") (pintype "passive"))
      (node (ref "U2") (pin "6") (pinfunction "TIMER_6") (pintype "bidirectional"))
    )
    (net (code "44") (name "Net-(U2-VFB)") (class "Default")
      (node (ref "R13") (pin "1") (pinfunction "1_1") (pintype "passive"))
      (node (ref "U2") (pin "7") (pinfunction "VFB_7") (pintype "bidirectional"))
    )
    (net (code "45") (name "Net-(U2-VIN_REG)") (class "Default")
      (node (ref "R6") (pin "1") (pinfunction "1_1") (pintype "passive"))
      (node (ref "R7") (pin "2") (pinfunction "2_2") (pintype "passive"))
      (node (ref "U2") (pin "2") (pinfunction "VIN_REG_2") (pintype "bidirectional"))
    )
    (net (code "46") (name "Net-(U2-~{CHRG})") (class "Default")
      (node (ref "R10") (pin "1") (pinfunction "1_1") (pintype "passive"))
      (node (ref "R3") (pin "1") (pinfunction "1_1") (pintype "passive"))
      (node (ref "R4") (pin "1") (pinfunction "1_1") (pintype "passive"))
      (node (ref "U2") (pin "4") (pinfunction "~{CHRG}_4") (pintype "bidirectional"))
    )
    (net (code "47") (name "Net-(U2-~{FAULT})") (class "Default")
      (node (ref "R5") (pin "1") (pinfunction "1_1") (pintype "passive"))
      (node (ref "U2") (pin "5") (pinfunction "~{FAULT}_5") (pintype "bidirectional"))
    )
    (net (code "48") (name "Net-(U2-~{SHDN})") (class "Default")
      (node (ref "SJ1") (pin "2") (pinfunction "2_2") (pintype "passive"))
      (node (ref "U2") (pin "3") (pinfunction "~{SHDN}_3") (pintype "bidirectional"))
    )
    (net (code "49") (name "Net-(U4-VBUS)") (class "Default")
      (node (ref "R16") (pin "2") (pinfunction "2_2") (pintype "passive"))
      (node (ref "SJ2") (pin "1") (pinfunction "1_1") (pintype "passive"))
      (node (ref "U4") (pin "8") (pinfunction "VBUS_8") (pintype "power_in"))
      (node (ref "U4") (pin "9") (pinfunction "VIN-_9") (pintype "bidirectional"))
    )
    (net (code "50") (name "Net-(U5-FB)") (class "Default")
      (node (ref "C17") (pin "2") (pinfunction "2_2") (pintype "passive"))
      (node (ref "R18") (pin "1") (pinfunction "1_1") (pintype "passive"))
      (node (ref "R19") (pin "1") (pinfunction "1_1") (pintype "passive"))
      (node (ref "U5") (pin "7") (pinfunction "FB_7") (pintype "bidirectional"))
    )
    (net (code "51") (name "Net-(U5-SS)") (class "Default")
      (node (ref "C16") (pin "1") (pinfunction "1_1") (pintype "passive"))
      (node (ref "U5") (pin "8") (pinfunction "SS_8") (pintype "bidirectional"))
    )
    (net (code "52") (name "Net-(U6-FB)") (class "Default")
      (node (ref "R20") (pin "1") (pinfunction "1_1") (pintype "passive"))
      (node (ref "R21") (pin "2") (pinfunction "2_2") (pintype "passive"))
      (node (ref "U6") (pin "2") (pinfunction "FB_2") (pintype "bidirectional"))
    )
    (net (code "53") (name "Net-(U6-SS)") (class "Default")
      (node (ref "C24") (pin "1") (pinfunction "1_1") (pintype "passive"))
      (node (ref "U6") (pin "1") (pinfunction "SS_1") (pintype "bidirectional"))
    )
    (net (code "54") (name "Net-(U7-PB6(XTAL1{slash}TOSC1))") (class "Default")
      (node (ref "C26") (pin "2") (pinfunction "2_2") (pintype "passive"))
      (node (ref "U7") (pin "7") (pinfunction "PB6(XTAL1/TOSC1)_7") (pintype "bidirectional"))
      (node (ref "Y1") (pin "1") (pinfunction "X1_1") (pintype "bidirectional"))
    )
    (net (code "55") (name "Net-(U7-PB7(XTAL2{slash}TOSC2))") (class "Default")
      (node (ref "C27") (pin "2") (pinfunction "2_2") (pintype "passive"))
      (node (ref "U7") (pin "8") (pinfunction "PB7(XTAL2/TOSC2)_8") (pintype "bidirectional"))
      (node (ref "Y1") (pin "3") (pinfunction "X2_3") (pintype "bidirectional"))
    )
    (net (code "56") (name "Net-(U8-OPTO_BIAS)") (class "Default")
      (node (ref "Q2") (pin "C") (pinfunction "C_C") (pintype "passive"))
      (node (ref "U8") (pin "2") (pinfunction "OPTO_BIAS_2") (pintype "bidirectional"))
    )
    (net (code "57") (name "Net-(U8-OPTO_IN)") (class "Default")
      (node (ref "Q2") (pin "E") (pinfunction "E_E") (pintype "passive"))
      (node (ref "R24") (pin "2") (pinfunction "2_2") (pintype "passive"))
      (node (ref "U8") (pin "6") (pinfunction "OPTO_IN_6") (pintype "bidirectional"))
    )
    (net (code "58") (name "VBATT") (class "Default")
      (node (ref "F2") (pin "2") (pinfunction "P$2_2") (pintype "bidirectional"))
      (node (ref "J2") (pin "P$1") (pinfunction "1_P$1") (pintype "bidirectional"))
    )
    (net (code "59") (name "VSOLAR") (class "Default")
      (node (ref "F1") (pin "1") (pinfunction "P$1_1") (pintype "bidirectional"))
      (node (ref "J1") (pin "P$1") (pinfunction "1_P$1") (pintype "bidirectional"))
    )
    (net (code "60") (name "VSUPPLY") (class "Default")
      (node (ref "C13") (pin "+") (pinfunction "+_+") (pintype "passive"))
      (node (ref "C14") (pin "1") (pinfunction "1_1") (pintype "passive"))
      (node (ref "C15") (pin "1") (pinfunction "1_1") (pintype "passive"))
      (node (ref "C22") (pin "1") (pinfunction "1_1") (pintype "passive"))
      (node (ref "SJ2") (pin "2") (pinfunction "2_2") (pintype "passive"))
      (node (ref "U5") (pin "1") (pinfunction "VIN_1") (pintype "bidirectional"))
      (node (ref "U5") (pin "2") (pinfunction "VIN_2") (pintype "bidirectional"))
      (node (ref "U6") (pin "7") (pinfunction "EN_7") (pintype "bidirectional"))
      (node (ref "U6") (pin "8") (pinfunction "VIN_8") (pintype "bidirectional"))
    )
    (net (code "61") (name "unconnected-(J8-Pad6)") (class "Default")
      (node (ref "J8") (pin "6") (pinfunction "6_6") (pintype "passive"))
    )
    (net (code "62") (name "unconnected-(J8-Pad14)") (class "Default")
      (node (ref "J8") (pin "14") (pinfunction "14_14") (pintype "passive"))
    )
    (net (code "63") (name "unconnected-(J8-Pad16)") (class "Default")
      (node (ref "J8") (pin "16") (pinfunction "16_16") (pintype "passive"))
    )
    (net (code "64") (name "unconnected-(U1-ALERT-Pad3)") (class "Default")
      (node (ref "U1") (pin "3") (pinfunction "ALERT_3") (pintype "bidirectional"))
    )
    (net (code "65") (name "unconnected-(U2-NTC-Pad8)") (class "Default")
      (node (ref "U2") (pin "8") (pinfunction "NTC_8") (pintype "bidirectional"))
    )
    (net (code "66") (name "unconnected-(U3-ALERT-Pad3)") (class "Default")
      (node (ref "U3") (pin "3") (pinfunction "ALERT_3") (pintype "bidirectional"))
    )
    (net (code "67") (name "unconnected-(U4-ALERT-Pad3)") (class "Default")
      (node (ref "U4") (pin "3") (pinfunction "ALERT_3") (pintype "bidirectional"))
    )
    (net (code "68") (name "unconnected-(U5-SH-Pad9)") (class "Default")
      (node (ref "U5") (pin "9") (pinfunction "SH_9") (pintype "bidirectional"))
    )
    (net (code "69") (name "unconnected-(U6-PG-Pad3)") (class "Default")
      (node (ref "U6") (pin "3") (pinfunction "PG_3") (pintype "bidirectional"))
    )
    (net (code "70") (name "unconnected-(U7-ADC6-Pad19)") (class "Default")
      (node (ref "U7") (pin "19") (pinfunction "ADC6_19") (pintype "bidirectional"))
    )
    (net (code "71") (name "unconnected-(U7-ADC7-Pad22)") (class "Default")
      (node (ref "U7") (pin "22") (pinfunction "ADC7_22") (pintype "bidirectional"))
    )
    (net (code "72") (name "unconnected-(U7-AREF-Pad20)") (class "Default")
      (node (ref "U7") (pin "20") (pinfunction "AREF_20") (pintype "bidirectional"))
    )
    (net (code "73") (name "unconnected-(U7-PB0(ICP)-Pad12)") (class "Default")
      (node (ref "U7") (pin "12") (pinfunction "PB0(ICP)_12") (pintype "bidirectional"))
    )
    (net (code "74") (name "unconnected-(U7-PB1(OC1A)-Pad13)") (class "Default")
      (node (ref "U7") (pin "13") (pinfunction "PB1(OC1A)_13") (pintype "bidirectional"))
    )
    (net (code "75") (name "unconnected-(U7-PB2(SS{slash}OC1B)-Pad14)") (class "Default")
      (node (ref "U7") (pin "14") (pinfunction "PB2(SS/OC1B)_14") (pintype "bidirectional"))
    )
    (net (code "76") (name "unconnected-(U7-PC0(ADC0)-Pad23)") (class "Default")
      (node (ref "U7") (pin "23") (pinfunction "PC0(ADC0)_23") (pintype "bidirectional"))
    )
    (net (code "77") (name "unconnected-(U7-PC1(ADC1)-Pad24)") (class "Default")
      (node (ref "U7") (pin "24") (pinfunction "PC1(ADC1)_24") (pintype "bidirectional"))
    )
    (net (code "78") (name "unconnected-(U7-PC2(ADC2)-Pad25)") (class "Default")
      (node (ref "U7") (pin "25") (pinfunction "PC2(ADC2)_25") (pintype "bidirectional"))
    )
    (net (code "79") (name "unconnected-(U7-PD4(XCK{slash}T0)-Pad2)") (class "Default")
      (node (ref "U7") (pin "2") (pinfunction "PD4(XCK/T0)_2") (pintype "bidirectional"))
    )
    (net (code "80") (name "unconnected-(U7-PD5(T1)-Pad9)") (class "Default")
      (node (ref "U7") (pin "9") (pinfunction "PD5(T1)_9") (pintype "bidirectional"))
    )
    (net (code "81") (name "unconnected-(U7-PD6(AIN0)-Pad10)") (class "Default")
      (node (ref "U7") (pin "10") (pinfunction "PD6(AIN0)_10") (pintype "bidirectional"))
    )
    (net (code "82") (name "unconnected-(U7-PD7(AIN1)-Pad11)") (class "Default")
      (node (ref "U7") (pin "11") (pinfunction "PD7(AIN1)_11") (pintype "bidirectional"))
    )
    (net (code "83") (name "unconnected-(U8-PIN_1-Pad15)") (class "Default")
      (node (ref "U8") (pin "15") (pinfunction "PIN_1_15") (pintype "bidirectional"))
    )
    (net (code "84") (name "unconnected-(U8-PIN_A-Pad8)") (class "Default")
      (node (ref "U8") (pin "8") (pinfunction "PIN_A_8") (pintype "bidirectional"))
    )
    (net (code "85") (name "unconnected-(U8-POWER_EN-Pad5)") (class "Default")
      (node (ref "U8") (pin "5") (pinfunction "POWER_EN_5") (pintype "bidirectional"))
    )
  )
)
